# Projet_Elec.net
KiCad netlist of a schematic drawn in EAGLE
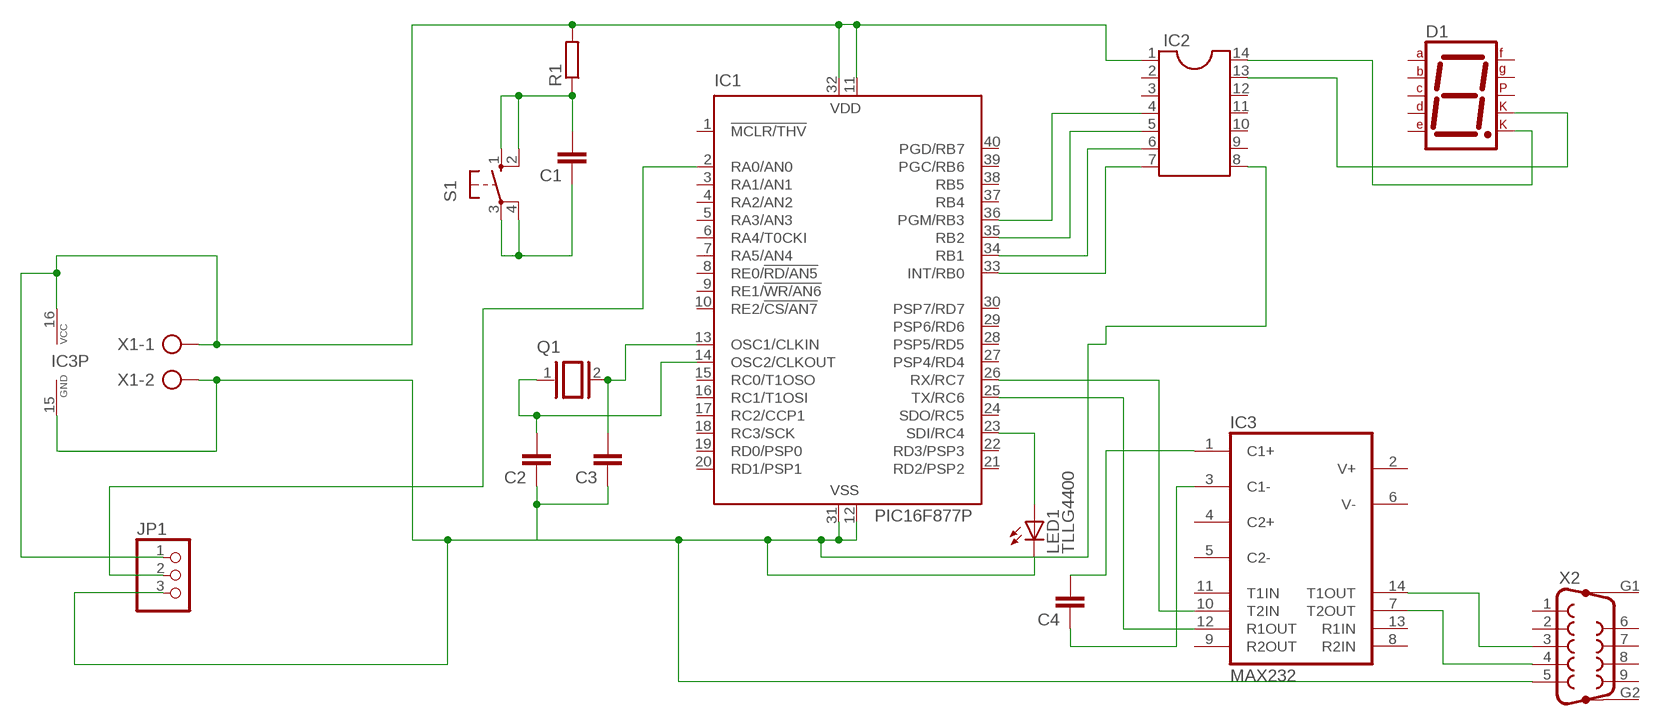
[diagram p0: schematic, sheet 1]

(export (version "E")
  (design (tool "Eeschema 10.0.6"))
  (components
    (comp (ref "C1")
      (value "C-EU025-025X050")
      (footprint "eagle-import:C025-025X050")
      (libsource (lib "eagle-import") (part "C-EU025-025X050"))
    )
    (comp (ref "C2")
      (value "C-EU025-024X044")
      (footprint "eagle-import:C025-024X044")
      (libsource (lib "eagle-import") (part "C-EU025-024X044"))
    )
    (comp (ref "C3")
      (value "C-EU025-024X044")
      (footprint "eagle-import:C025-024X044")
      (libsource (lib "eagle-import") (part "C-EU025-024X044"))
    )
    (comp (ref "C4")
      (value "C-EU025-024X044")
      (footprint "eagle-import:C025-024X044")
      (libsource (lib "eagle-import") (part "C-EU025-024X044"))
    )
    (comp (ref "D1")
      (value "7SEG-CK")
      (footprint "eagle-import:7SEG-13")
      (libsource (lib "eagle-import") (part "7SEG-CK"))
    )
    (comp (ref "IC1")
      (value "PIC16F877P")
      (footprint "eagle-import:DIL40")
      (fields (field (name "MF") "MICROCHIP") (field (name "MPN") "PIC16F877-04/P"))
      (libsource (lib "eagle-import") (part "PIC16F87P7"))
    )
    (comp (ref "IC2")
      (value "DIL14")
      (footprint "eagle-import:DIL14")
      (libsource (lib "eagle-import") (part "DIL14"))
    )
    (comp (ref "IC3")
      (value "MAX232")
      (footprint "eagle-import:DIL16")
      (fields (field (name "MF") "MAXIM") (field (name "MPN") "MAX232ACPE+"))
      (libsource (lib "eagle-import") (part "MAX232"))
    )
    (comp (ref "JP1")
      (value "PINHD-1X3")
      (footprint "eagle-import:1X03")
      (libsource (lib "eagle-import") (part "PINHD-1X3"))
    )
    (comp (ref "LED1")
      (value "TLLG4400")
      (footprint "eagle-import:LED3MM")
      (fields (field (name "MF") "VISHAY SEMICONDUCTOR"))
      (libsource (lib "eagle-import") (part "TLLG4400"))
    )
    (comp (ref "Q1")
      (value "XTAL/S")
      (footprint "eagle-import:QS")
      (libsource (lib "eagle-import") (part "XTAL/S"))
    )
    (comp (ref "R1")
      (value "R-EU_0207/10")
      (footprint "eagle-import:0207_10")
      (libsource (lib "eagle-import") (part "R-EU_0207/10"))
    )
    (comp (ref "S1")
      (value "10-XX")
      (footprint "eagle-import:B3F-10XX")
      (fields (field (name "MPN") "B3F-1000"))
      (libsource (lib "eagle-import") (part "10-XX"))
    )
    (comp (ref "X1")
      (value "AK300/2")
      (footprint "eagle-import:AK300_2")
      (libsource (lib "eagle-import") (part "AK300/2"))
    )
    (comp (ref "X2")
      (value "F09VP")
      (footprint "eagle-import:F09VP")
      (libsource (lib "eagle-import") (part "F09VP"))
    )
  )
  (nets
    (net (code "1") (name "Net-(D1-CK1)") (class "Default")
      (node (ref "D1") (pin "3") (pinfunction "CK1_3") (pintype "passive"))
      (node (ref "IC2") (pin "13") (pinfunction "13_13") (pintype "passive"))
    )
    (net (code "2") (name "Net-(D1-CK2)") (class "Default")
      (node (ref "D1") (pin "8") (pinfunction "CK2_8") (pintype "passive"))
      (node (ref "IC2") (pin "14") (pinfunction "14_14") (pintype "passive"))
    )
    (net (code "3") (name "Net-(IC1-INT{slash}RB0)") (class "Default")
      (node (ref "IC1") (pin "33") (pinfunction "INT/RB0_33") (pintype "bidirectional"))
      (node (ref "IC2") (pin "7") (pinfunction "7_7") (pintype "passive"))
    )
    (net (code "4") (name "Net-(IC1-OSC1{slash}CLKIN)") (class "Default")
      (node (ref "C3") (pin "2") (pinfunction "2_2") (pintype "passive"))
      (node (ref "IC1") (pin "13") (pinfunction "OSC1/CLKIN_13") (pintype "input"))
      (node (ref "Q1") (pin "2") (pinfunction "2_2") (pintype "passive"))
    )
    (net (code "5") (name "Net-(IC1-OSC2{slash}CLKOUT)") (class "Default")
      (node (ref "C2") (pin "2") (pinfunction "2_2") (pintype "passive"))
      (node (ref "IC1") (pin "14") (pinfunction "OSC2/CLKOUT_14") (pintype "output"))
      (node (ref "Q1") (pin "1") (pinfunction "1_1") (pintype "passive"))
    )
    (net (code "6") (name "Net-(IC1-PGM{slash}RB3)") (class "Default")
      (node (ref "IC1") (pin "36") (pinfunction "PGM/RB3_36") (pintype "bidirectional"))
      (node (ref "IC2") (pin "4") (pinfunction "4_4") (pintype "passive"))
    )
    (net (code "7") (name "Net-(IC1-RA0{slash}AN0)") (class "Default")
      (node (ref "IC1") (pin "2") (pinfunction "RA0/AN0_2") (pintype "bidirectional"))
      (node (ref "JP1") (pin "2") (pinfunction "2_2") (pintype "passive"))
    )
    (net (code "8") (name "Net-(IC1-RB1)") (class "Default")
      (node (ref "IC1") (pin "34") (pinfunction "RB1_34") (pintype "bidirectional"))
      (node (ref "IC2") (pin "6") (pinfunction "6_6") (pintype "passive"))
    )
    (net (code "9") (name "Net-(IC1-RB2)") (class "Default")
      (node (ref "IC1") (pin "35") (pinfunction "RB2_35") (pintype "bidirectional"))
      (node (ref "IC2") (pin "5") (pinfunction "5_5") (pintype "passive"))
    )
    (net (code "10") (name "Net-(IC1-RX{slash}RC7)") (class "Default")
      (node (ref "IC1") (pin "26") (pinfunction "RX/RC7_26") (pintype "bidirectional"))
      (node (ref "IC3") (pin "10") (pinfunction "T2IN_10") (pintype "input"))
    )
    (net (code "11") (name "Net-(IC1-SDI{slash}RC4)") (class "Default")
      (node (ref "IC1") (pin "23") (pinfunction "SDI/RC4_23") (pintype "bidirectional"))
      (node (ref "LED1") (pin "A") (pinfunction "A_A") (pintype "passive"))
    )
    (net (code "12") (name "Net-(IC1-TX{slash}RC6)") (class "Default")
      (node (ref "IC1") (pin "25") (pinfunction "TX/RC6_25") (pintype "bidirectional"))
      (node (ref "IC3") (pin "12") (pinfunction "R1OUT_12") (pintype "output"))
    )
    (net (code "13") (name "Net-(IC3A-C1+)") (class "Default")
      (node (ref "C4") (pin "2") (pinfunction "2_2") (pintype "passive"))
      (node (ref "IC3") (pin "1") (pinfunction "C1+_1") (pintype "bidirectional"))
    )
    (net (code "14") (name "Net-(IC3A-C1-)") (class "Default")
      (node (ref "C4") (pin "1") (pinfunction "1_1") (pintype "passive"))
      (node (ref "IC3") (pin "3") (pinfunction "C1-_3") (pintype "bidirectional"))
    )
    (net (code "15") (name "Net-(IC3A-T1OUT)") (class "Default")
      (node (ref "IC3") (pin "14") (pinfunction "T1OUT_14") (pintype "output"))
      (node (ref "X2") (pin "3") (pinfunction "3_3") (pintype "passive"))
    )
    (net (code "16") (name "Net-(IC3A-T2OUT)") (class "Default")
      (node (ref "IC3") (pin "7") (pinfunction "T2OUT_7") (pintype "output"))
      (node (ref "X2") (pin "4") (pinfunction "4_4") (pintype "passive"))
    )
    (net (code "17") (name "Net-(IC3B-GND)") (class "Default")
      (node (ref "C2") (pin "1") (pinfunction "1_1") (pintype "passive"))
      (node (ref "C3") (pin "1") (pinfunction "1_1") (pintype "passive"))
      (node (ref "IC1") (pin "12") (pinfunction "VSS_12") (pintype "power_in"))
      (node (ref "IC1") (pin "31") (pinfunction "VSS_31") (pintype "power_in"))
      (node (ref "IC2") (pin "8") (pinfunction "8_8") (pintype "passive"))
      (node (ref "IC3") (pin "15") (pinfunction "GND_15") (pintype "power_in"))
      (node (ref "JP1") (pin "3") (pinfunction "3_3") (pintype "passive"))
      (node (ref "LED1") (pin "K") (pinfunction "C_K") (pintype "passive"))
      (node (ref "X1") (pin "2") (pinfunction "KL_2") (pintype "passive"))
      (node (ref "X2") (pin "5") (pinfunction "5_5") (pintype "passive"))
    )
    (net (code "18") (name "Net-(IC3B-VCC)") (class "Default")
      (node (ref "IC1") (pin "11") (pinfunction "VDD_11") (pintype "power_in"))
      (node (ref "IC1") (pin "32") (pinfunction "VDD_32") (pintype "power_in"))
      (node (ref "IC2") (pin "1") (pinfunction "1_1") (pintype "passive"))
      (node (ref "IC3") (pin "16") (pinfunction "VCC_16") (pintype "power_in"))
      (node (ref "JP1") (pin "1") (pinfunction "1_1") (pintype "passive"))
      (node (ref "R1") (pin "2") (pinfunction "2_2") (pintype "passive"))
      (node (ref "X1") (pin "1") (pinfunction "KL_1") (pintype "passive"))
    )
    (net (code "19") (name "Net-(S1-P)") (class "Default")
      (node (ref "C1") (pin "1") (pinfunction "1_1") (pintype "passive"))
      (node (ref "S1") (pin "3") (pinfunction "P_3") (pintype "passive"))
      (node (ref "S1") (pin "4") (pinfunction "P1_4") (pintype "passive"))
    )
    (net (code "20") (name "Net-(S1-S)") (class "Default")
      (node (ref "C1") (pin "2") (pinfunction "2_2") (pintype "passive"))
      (node (ref "R1") (pin "1") (pinfunction "1_1") (pintype "passive"))
      (node (ref "S1") (pin "1") (pinfunction "S_1") (pintype "passive"))
      (node (ref "S1") (pin "2") (pinfunction "S1_2") (pintype "passive"))
    )
    (net (code "21") (name "unconnected-(D1-A-Pad7)") (class "Default")
      (node (ref "D1") (pin "7") (pinfunction "A_7") (pintype "passive"))
    )
    (net (code "22") (name "unconnected-(D1-B-Pad6)") (class "Default")
      (node (ref "D1") (pin "6") (pinfunction "B_6") (pintype "passive"))
    )
    (net (code "23") (name "unconnected-(D1-C-Pad4)") (class "Default")
      (node (ref "D1") (pin "4") (pinfunction "C_4") (pintype "passive"))
    )
    (net (code "24") (name "unconnected-(D1-D-Pad2)") (class "Default")
      (node (ref "D1") (pin "2") (pinfunction "D_2") (pintype "passive"))
    )
    (net (code "25") (name "unconnected-(D1-DP-Pad5)") (class "Default")
      (node (ref "D1") (pin "5") (pinfunction "DP_5") (pintype "passive"))
    )
    (net (code "26") (name "unconnected-(D1-E-Pad1)") (class "Default")
      (node (ref "D1") (pin "1") (pinfunction "E_1") (pintype "passive"))
    )
    (net (code "27") (name "unconnected-(D1-F-Pad9)") (class "Default")
      (node (ref "D1") (pin "9") (pinfunction "F_9") (pintype "passive"))
    )
    (net (code "28") (name "unconnected-(D1-G-Pad10)") (class "Default")
      (node (ref "D1") (pin "10") (pinfunction "G_10") (pintype "passive"))
    )
    (net (code "29") (name "unconnected-(IC1-PGC{slash}RB6-Pad39)") (class "Default")
      (node (ref "IC1") (pin "39") (pinfunction "PGC/RB6_39") (pintype "bidirectional"))
    )
    (net (code "30") (name "unconnected-(IC1-PGD{slash}RB7-Pad40)") (class "Default")
      (node (ref "IC1") (pin "40") (pinfunction "PGD/RB7_40") (pintype "bidirectional"))
    )
    (net (code "31") (name "unconnected-(IC1-PSP4{slash}RD4-Pad27)") (class "Default")
      (node (ref "IC1") (pin "27") (pinfunction "PSP4/RD4_27") (pintype "bidirectional"))
    )
    (net (code "32") (name "unconnected-(IC1-PSP5{slash}RD5-Pad28)") (class "Default")
      (node (ref "IC1") (pin "28") (pinfunction "PSP5/RD5_28") (pintype "bidirectional"))
    )
    (net (code "33") (name "unconnected-(IC1-PSP6{slash}RD6-Pad29)") (class "Default")
      (node (ref "IC1") (pin "29") (pinfunction "PSP6/RD6_29") (pintype "bidirectional"))
    )
    (net (code "34") (name "unconnected-(IC1-PSP7{slash}RD7-Pad30)") (class "Default")
      (node (ref "IC1") (pin "30") (pinfunction "PSP7/RD7_30") (pintype "bidirectional"))
    )
    (net (code "35") (name "unconnected-(IC1-RA1{slash}AN1-Pad3)") (class "Default")
      (node (ref "IC1") (pin "3") (pinfunction "RA1/AN1_3") (pintype "bidirectional"))
    )
    (net (code "36") (name "unconnected-(IC1-RA2{slash}AN2-Pad4)") (class "Default")
      (node (ref "IC1") (pin "4") (pinfunction "RA2/AN2_4") (pintype "bidirectional"))
    )
    (net (code "37") (name "unconnected-(IC1-RA3{slash}AN3-Pad5)") (class "Default")
      (node (ref "IC1") (pin "5") (pinfunction "RA3/AN3_5") (pintype "bidirectional"))
    )
    (net (code "38") (name "unconnected-(IC1-RA4{slash}T0CKI-Pad6)") (class "Default")
      (node (ref "IC1") (pin "6") (pinfunction "RA4/T0CKI_6") (pintype "bidirectional"))
    )
    (net (code "39") (name "unconnected-(IC1-RA5{slash}AN4-Pad7)") (class "Default")
      (node (ref "IC1") (pin "7") (pinfunction "RA5/AN4_7") (pintype "bidirectional"))
    )
    (net (code "40") (name "unconnected-(IC1-RB4-Pad37)") (class "Default")
      (node (ref "IC1") (pin "37") (pinfunction "RB4_37") (pintype "bidirectional"))
    )
    (net (code "41") (name "unconnected-(IC1-RB5-Pad38)") (class "Default")
      (node (ref "IC1") (pin "38") (pinfunction "RB5_38") (pintype "bidirectional"))
    )
    (net (code "42") (name "unconnected-(IC1-RC0{slash}T1OSO-Pad15)") (class "Default")
      (node (ref "IC1") (pin "15") (pinfunction "RC0/T1OSO_15") (pintype "bidirectional"))
    )
    (net (code "43") (name "unconnected-(IC1-RC1{slash}T1OSI-Pad16)") (class "Default")
      (node (ref "IC1") (pin "16") (pinfunction "RC1/T1OSI_16") (pintype "bidirectional"))
    )
    (net (code "44") (name "unconnected-(IC1-RC2{slash}CCP1-Pad17)") (class "Default")
      (node (ref "IC1") (pin "17") (pinfunction "RC2/CCP1_17") (pintype "bidirectional"))
    )
    (net (code "45") (name "unconnected-(IC1-RC3{slash}SCK-Pad18)") (class "Default")
      (node (ref "IC1") (pin "18") (pinfunction "RC3/SCK_18") (pintype "bidirectional"))
    )
    (net (code "46") (name "unconnected-(IC1-RD0{slash}PSP0-Pad19)") (class "Default")
      (node (ref "IC1") (pin "19") (pinfunction "RD0/PSP0_19") (pintype "bidirectional"))
    )
    (net (code "47") (name "unconnected-(IC1-RD1{slash}PSP1-Pad20)") (class "Default")
      (node (ref "IC1") (pin "20") (pinfunction "RD1/PSP1_20") (pintype "bidirectional"))
    )
    (net (code "48") (name "unconnected-(IC1-RD2{slash}PSP2-Pad21)") (class "Default")
      (node (ref "IC1") (pin "21") (pinfunction "RD2/PSP2_21") (pintype "bidirectional"))
    )
    (net (code "49") (name "unconnected-(IC1-RD3{slash}PSP3-Pad22)") (class "Default")
      (node (ref "IC1") (pin "22") (pinfunction "RD3/PSP3_22") (pintype "bidirectional"))
    )
    (net (code "50") (name "unconnected-(IC1-RE0{slash}~{RD{slash}AN5}-Pad8)") (class "Default")
      (node (ref "IC1") (pin "8") (pinfunction "RE0/~{RD/AN5}_8") (pintype "bidirectional"))
    )
    (net (code "51") (name "unconnected-(IC1-RE1{slash}~{WR{slash}AN6}-Pad9)") (class "Default")
      (node (ref "IC1") (pin "9") (pinfunction "RE1/~{WR/AN6}_9") (pintype "bidirectional"))
    )
    (net (code "52") (name "unconnected-(IC1-RE2{slash}~{CS{slash}AN7}-Pad10)") (class "Default")
      (node (ref "IC1") (pin "10") (pinfunction "RE2/~{CS/AN7}_10") (pintype "bidirectional"))
    )
    (net (code "53") (name "unconnected-(IC1-SDO{slash}RC5-Pad24)") (class "Default")
      (node (ref "IC1") (pin "24") (pinfunction "SDO/RC5_24") (pintype "bidirectional"))
    )
    (net (code "54") (name "unconnected-(IC1-~{MCLR{slash}THV}-Pad1)") (class "Default")
      (node (ref "IC1") (pin "1") (pinfunction "~{MCLR/THV}_1") (pintype "input"))
    )
    (net (code "55") (name "unconnected-(IC2-Pad2)") (class "Default")
      (node (ref "IC2") (pin "2") (pinfunction "2_2") (pintype "passive"))
    )
    (net (code "56") (name "unconnected-(IC2-Pad3)") (class "Default")
      (node (ref "IC2") (pin "3") (pinfunction "3_3") (pintype "passive"))
    )
    (net (code "57") (name "unconnected-(IC2-Pad9)") (class "Default")
      (node (ref "IC2") (pin "9") (pinfunction "9_9") (pintype "passive"))
    )
    (net (code "58") (name "unconnected-(IC2-Pad10)") (class "Default")
      (node (ref "IC2") (pin "10") (pinfunction "10_10") (pintype "passive"))
    )
    (net (code "59") (name "unconnected-(IC2-Pad11)") (class "Default")
      (node (ref "IC2") (pin "11") (pinfunction "11_11") (pintype "passive"))
    )
    (net (code "60") (name "unconnected-(IC2-Pad12)") (class "Default")
      (node (ref "IC2") (pin "12") (pinfunction "12_12") (pintype "passive"))
    )
    (net (code "61") (name "unconnected-(IC3A-C2+-Pad4)") (class "Default")
      (node (ref "IC3") (pin "4") (pinfunction "C2+_4") (pintype "bidirectional"))
    )
    (net (code "62") (name "unconnected-(IC3A-C2--Pad5)") (class "Default")
      (node (ref "IC3") (pin "5") (pinfunction "C2-_5") (pintype "bidirectional"))
    )
    (net (code "63") (name "unconnected-(IC3A-R1IN-Pad13)") (class "Default")
      (node (ref "IC3") (pin "13") (pinfunction "R1IN_13") (pintype "input"))
    )
    (net (code "64") (name "unconnected-(IC3A-R2IN-Pad8)") (class "Default")
      (node (ref "IC3") (pin "8") (pinfunction "R2IN_8") (pintype "input"))
    )
    (net (code "65") (name "unconnected-(IC3A-R2OUT-Pad9)") (class "Default")
      (node (ref "IC3") (pin "9") (pinfunction "R2OUT_9") (pintype "output"))
    )
    (net (code "66") (name "unconnected-(IC3A-T1IN-Pad11)") (class "Default")
      (node (ref "IC3") (pin "11") (pinfunction "T1IN_11") (pintype "input"))
    )
    (net (code "67") (name "unconnected-(IC3A-V+-Pad2)") (class "Default")
      (node (ref "IC3") (pin "2") (pinfunction "V+_2") (pintype "bidirectional"))
    )
    (net (code "68") (name "unconnected-(IC3A-V--Pad6)") (class "Default")
      (node (ref "IC3") (pin "6") (pinfunction "V-_6") (pintype "bidirectional"))
    )
    (net (code "69") (name "unconnected-(X2-Pad1)") (class "Default")
      (node (ref "X2") (pin "1") (pinfunction "1_1") (pintype "passive"))
    )
    (net (code "70") (name "unconnected-(X2-Pad2)") (class "Default")
      (node (ref "X2") (pin "2") (pinfunction "2_2") (pintype "passive"))
    )
    (net (code "71") (name "unconnected-(X2-Pad6)") (class "Default")
      (node (ref "X2") (pin "6") (pinfunction "6_6") (pintype "passive"))
    )
    (net (code "72") (name "unconnected-(X2-Pad7)") (class "Default")
      (node (ref "X2") (pin "7") (pinfunction "7_7") (pintype "passive"))
    )
    (net (code "73") (name "unconnected-(X2-Pad8)") (class "Default")
      (node (ref "X2") (pin "8") (pinfunction "8_8") (pintype "passive"))
    )
    (net (code "74") (name "unconnected-(X2-Pad9)") (class "Default")
      (node (ref "X2") (pin "9") (pinfunction "9_9") (pintype "passive"))
    )
    (net (code "75") (name "unconnected-(X2-PadG1)") (class "Default")
      (node (ref "X2") (pin "G1") (pinfunction "G1_G1") (pintype "passive"))
    )
    (net (code "76") (name "unconnected-(X2-PadG2)") (class "Default")
      (node (ref "X2") (pin "G2") (pinfunction "G2_G2") (pintype "passive"))
    )
  )
)
